# CAN.net
KiCad netlist of a schematic drawn in Altium Designer
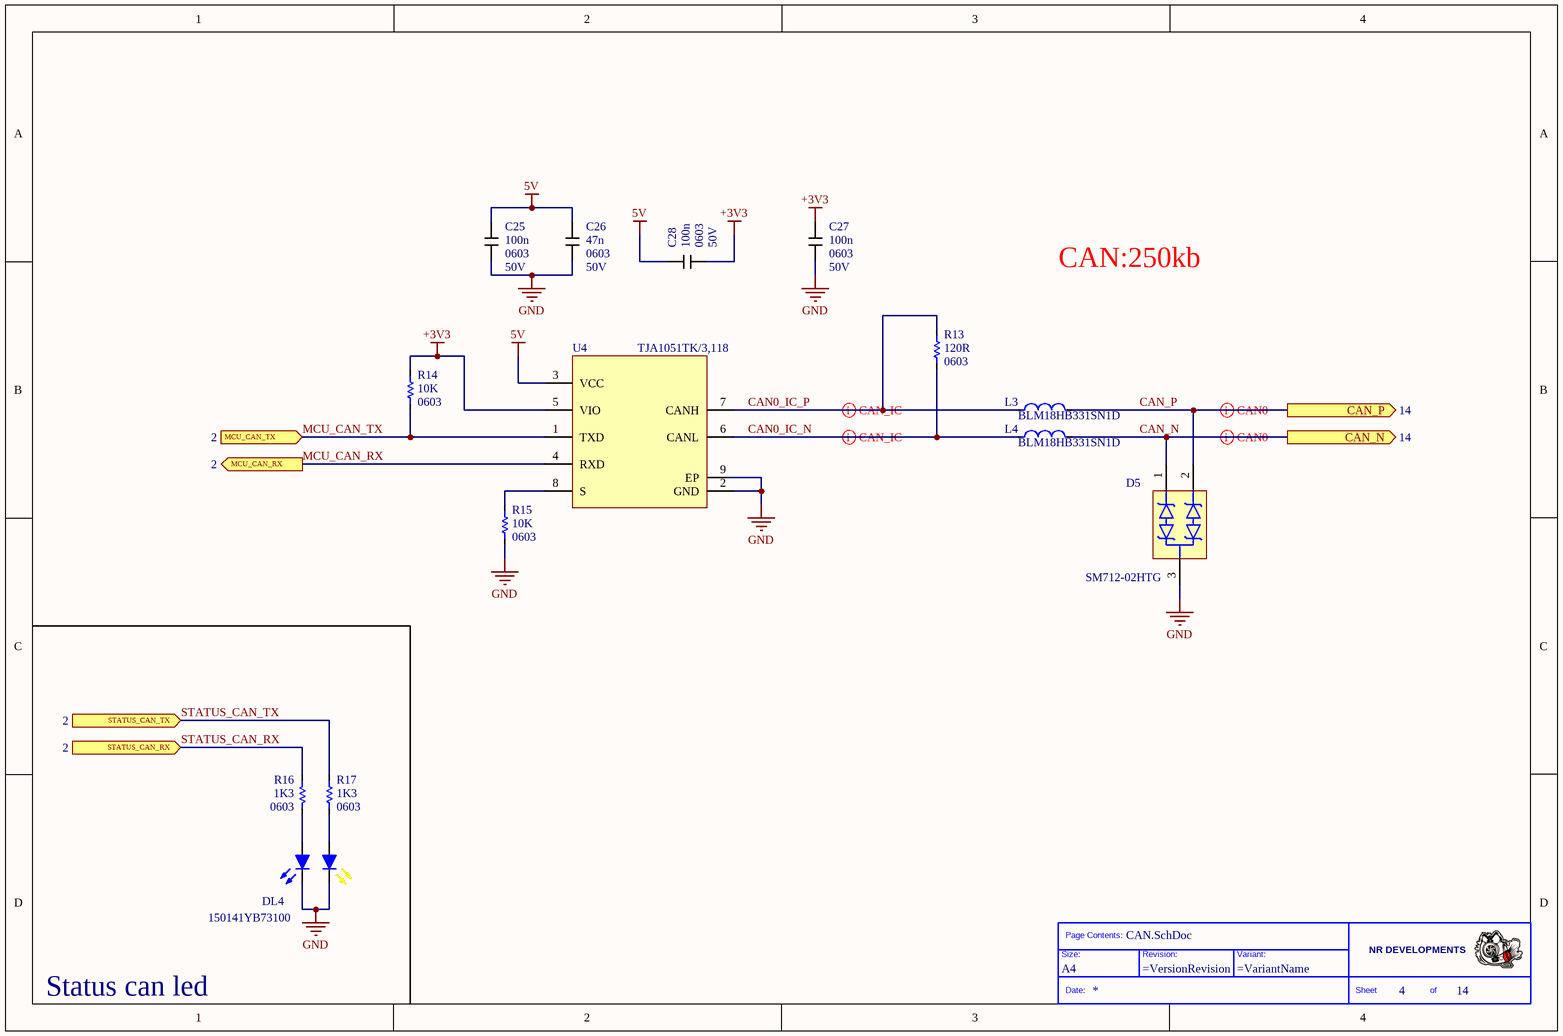
[diagram p0: CAN.SchDoc]

(export (version "E")
  (design (tool "Eeschema 10.0.6"))
  (components
    (comp (ref "C25")
      (value "100n")
      (footprint "CAPC1608X09M")
      (fields
        (field (name "CASE") "0603")
        (field (name "VOLTAGE") "50V")
        (field (name "MANUFACTURER") "KEMET")
        (field (name "PARTNUMBER") "C0603C104K5RACTU")
        (field (name "Comment") "CAP")
      )
      (libsource (lib "My_LIB") (part "CAP"))
    )
    (comp (ref "C26")
      (value "47n")
      (footprint "CAPC1608X09M")
      (fields
        (field (name "CASE") "0603")
        (field (name "VOLTAGE") "50V")
        (field (name "MANUFACTURER") "YAGEO")
        (field (name "PARTNUMBER") "CC0603KRX7R9BB473")
        (field (name "Comment") "CAP")
      )
      (libsource (lib "My_LIB") (part "CAP"))
    )
    (comp (ref "C27")
      (value "100n")
      (footprint "CAPC1608X09M")
      (fields
        (field (name "CASE") "0603")
        (field (name "VOLTAGE") "50V")
        (field (name "MANUFACTURER") "KEMET")
        (field (name "PARTNUMBER") "C0603C104K5RACTU")
        (field (name "Comment") "CAP")
      )
      (libsource (lib "My_LIB") (part "CAP"))
    )
    (comp (ref "C28")
      (value "100n")
      (footprint "CAPC1608X09M")
      (fields
        (field (name "CASE") "0603")
        (field (name "VOLTAGE") "50V")
        (field (name "MANUFACTURER") "KEMET")
        (field (name "PARTNUMBER") "C0603C104K5RACTU")
        (field (name "Comment") "CAP")
      )
      (libsource (lib "My_LIB") (part "CAP"))
    )
    (comp (ref "D5")
      (value "SM712-02HTG")
      (footprint "SOT95P240X120-3N")
      (description "ESD Diode bid")
      (fields (field (name "MANUFACTURER") "Littelfuse") (field (name "Comment") "ESD_Diode"))
      (libsource (lib "My_LIB") (part "SM712-02HTG"))
    )
    (comp (ref "DL4")
      (value "150141YB73100")
      (footprint "WURTH-SBTW_3528")
      (description "Led Yellow - Blue 3528")
      (fields (field (name "MANUFACTURER") "Wurth") (field (name "Comment") "LED_Yellow_Blue"))
      (libsource (lib "My_LIB") (part "LED_Yellow_Blue"))
    )
    (comp (ref "L3")
      (value "BLM18HB331SN1D")
      (footprint "INDC1608X09N")
      (fields (field (name "MANUFACTURER") "Murata") (field (name "Comment") "IND"))
      (libsource (lib "My_LIB") (part "IND"))
    )
    (comp (ref "L4")
      (value "BLM18HB331SN1D")
      (footprint "INDC1608X09N")
      (fields (field (name "MANUFACTURER") "Murata") (field (name "Comment") "IND"))
      (libsource (lib "My_LIB") (part "IND"))
    )
    (comp (ref "R13")
      (value "120R")
      (footprint "RESC1608X06M")
      (fields
        (field (name "CASE") "0603")
        (field (name "MANUFACTURER") "Vishay")
        (field (name "PARTNUMBER") "CRCW0603120RFKEA")
        (field (name "Comment") "Res")
      )
      (libsource (lib "My_LIB") (part "Resistor"))
    )
    (comp (ref "R14")
      (value "10K")
      (footprint "RESC1608X06M")
      (fields
        (field (name "CASE") "0603")
        (field (name "MANUFACTURER") "YAGEO")
        (field (name "PARTNUMBER") "AC0603FR-0710KL")
        (field (name "Comment") "Res")
      )
      (libsource (lib "My_LIB") (part "Resistor"))
    )
    (comp (ref "R15")
      (value "10K")
      (footprint "RESC1608X06M")
      (fields
        (field (name "CASE") "0603")
        (field (name "MANUFACTURER") "YAGEO")
        (field (name "PARTNUMBER") "AC0603FR-0710KL")
        (field (name "Comment") "Res")
      )
      (libsource (lib "My_LIB") (part "Resistor"))
    )
    (comp (ref "R16")
      (value "1K3")
      (footprint "RESC1608X06M")
      (fields
        (field (name "CASE") "0603")
        (field (name "MANUFACTURER") "Vishay")
        (field (name "PARTNUMBER") "RC0603FR-071K3L")
        (field (name "Comment") "Res")
      )
      (libsource (lib "My_LIB") (part "Resistor"))
    )
    (comp (ref "R17")
      (value "1K3")
      (footprint "RESC1608X06M")
      (fields
        (field (name "CASE") "0603")
        (field (name "MANUFACTURER") "Vishay")
        (field (name "PARTNUMBER") "RC0603FR-071K3L")
        (field (name "Comment") "Res")
      )
      (libsource (lib "My_LIB") (part "Resistor"))
    )
    (comp (ref "U4")
      (value "TJA1051TK/3,118")
      (footprint "SON65P300X300X100-9N-D")
      (description "CAN HIGH-SPEED CAN TRANSCEIVER 3.3V / 5V Pin VIO")
      (fields (field (name "MANUFACTURER") "NXP Semiconductors"))
      (libsource (lib "My_LIB") (part "TJA1051TK/3"))
    )
  )
  (nets
    (net (code "1") (name "+3V3") (class "Default")
      (node (ref "C27") (pin "1") (pinfunction "1_1") (pintype "passive"))
      (node (ref "C28") (pin "2") (pinfunction "2_2") (pintype "passive"))
      (node (ref "R14") (pin "2") (pinfunction "2_2") (pintype "passive"))
      (node (ref "U4") (pin "5") (pinfunction "VIO_5") (pintype "power_in"))
    )
    (net (code "2") (name "/CAN0_IC_N") (class "Default")
      (node (ref "L4") (pin "1") (pinfunction "1_1") (pintype "passive"))
      (node (ref "R13") (pin "1") (pinfunction "1_1") (pintype "passive"))
      (node (ref "U4") (pin "6") (pinfunction "CANL_6") (pintype "power_in"))
    )
    (net (code "3") (name "/CAN0_IC_P") (class "Default")
      (node (ref "L3") (pin "1") (pinfunction "1_1") (pintype "passive"))
      (node (ref "R13") (pin "2") (pinfunction "2_2") (pintype "passive"))
      (node (ref "U4") (pin "7") (pinfunction "CANH_7") (pintype "power_in"))
    )
    (net (code "4") (name "/CAN_N") (class "Default")
      (node (ref "D5") (pin "1") (pinfunction "1_1") (pintype "passive"))
      (node (ref "L4") (pin "2") (pinfunction "2_2") (pintype "passive"))
    )
    (net (code "5") (name "/CAN_P") (class "Default")
      (node (ref "D5") (pin "2") (pinfunction "2_2") (pintype "passive"))
      (node (ref "L3") (pin "2") (pinfunction "2_2") (pintype "passive"))
    )
    (net (code "6") (name "/MCU_CAN_RX") (class "Default")
      (node (ref "U4") (pin "4") (pinfunction "RXD_4") (pintype "passive"))
    )
    (net (code "7") (name "/MCU_CAN_TX") (class "Default")
      (node (ref "R14") (pin "1") (pinfunction "1_1") (pintype "passive"))
      (node (ref "U4") (pin "1") (pinfunction "TXD_1") (pintype "passive"))
    )
    (net (code "8") (name "/STATUS_CAN_RX") (class "Default")
      (node (ref "R16") (pin "2") (pinfunction "2_2") (pintype "passive"))
    )
    (net (code "9") (name "/STATUS_CAN_TX") (class "Default")
      (node (ref "R17") (pin "2") (pinfunction "2_2") (pintype "passive"))
    )
    (net (code "10") (name "5V") (class "Default")
      (node (ref "C25") (pin "1") (pinfunction "1_1") (pintype "passive"))
      (node (ref "C26") (pin "1") (pinfunction "1_1") (pintype "passive"))
      (node (ref "C28") (pin "1") (pinfunction "1_1") (pintype "passive"))
      (node (ref "U4") (pin "3") (pinfunction "VCC_3") (pintype "power_in"))
    )
    (net (code "11") (name "GND") (class "Default")
      (node (ref "C25") (pin "2") (pinfunction "2_2") (pintype "passive"))
      (node (ref "C26") (pin "2") (pinfunction "2_2") (pintype "passive"))
      (node (ref "C27") (pin "2") (pinfunction "2_2") (pintype "passive"))
      (node (ref "D5") (pin "3") (pinfunction "3_3") (pintype "passive"))
      (node (ref "DL4") (pin "C1") (pinfunction "C1_C1") (pintype "passive"))
      (node (ref "DL4") (pin "C2") (pinfunction "C2_C2") (pintype "passive"))
      (node (ref "R15") (pin "1") (pinfunction "1_1") (pintype "passive"))
      (node (ref "U4") (pin "2") (pinfunction "GND_2") (pintype "power_in"))
      (node (ref "U4") (pin "9") (pinfunction "EP_9") (pintype "power_in"))
    )
    (net (code "12") (name "Net-(DL4-PadA1)") (class "Default")
      (node (ref "DL4") (pin "A1") (pinfunction "A1_A1") (pintype "passive"))
      (node (ref "R17") (pin "1") (pinfunction "1_1") (pintype "passive"))
    )
    (net (code "13") (name "Net-(DL4-PadA2)") (class "Default")
      (node (ref "DL4") (pin "A2") (pinfunction "A2_A2") (pintype "passive"))
      (node (ref "R16") (pin "1") (pinfunction "1_1") (pintype "passive"))
    )
    (net (code "14") (name "Net-(U4-S)") (class "Default")
      (node (ref "R15") (pin "2") (pinfunction "2_2") (pintype "passive"))
      (node (ref "U4") (pin "8") (pinfunction "S_8") (pintype "power_in"))
    )
  )
)
